# B_Sensor_Board_Digital_v1_2.net
KiCad netlist of a schematic drawn in EAGLE
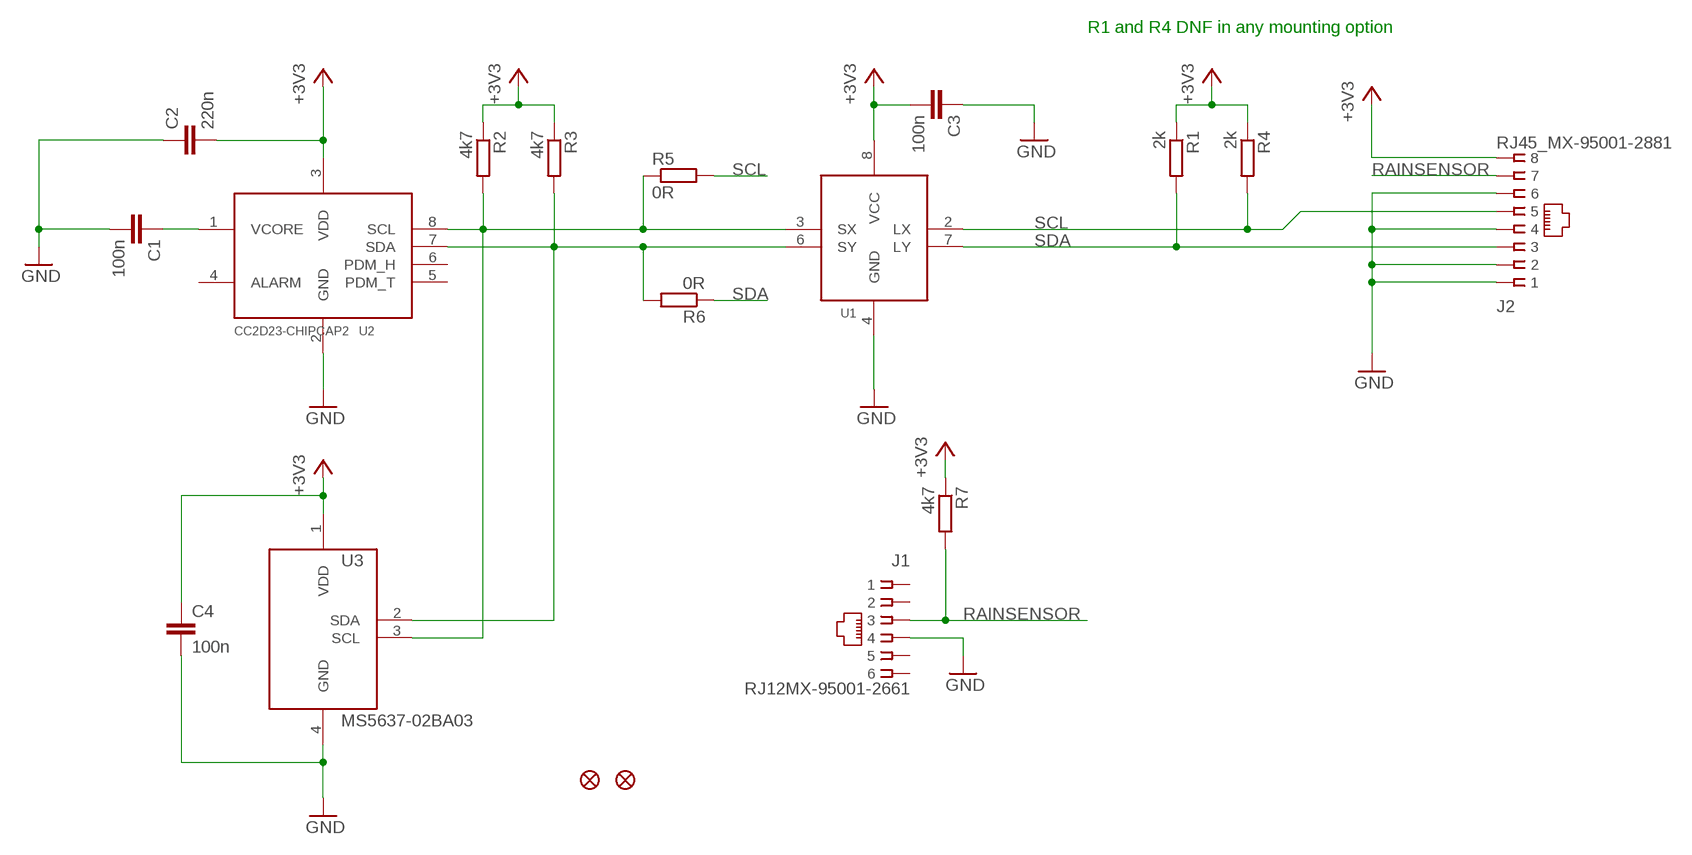
[diagram p0: schematic, sheet 1]

(export (version "E")
  (design (tool "Eeschema 10.0.6"))
  (components
    (comp (ref "C1")
      (value "100n")
      (footprint "eagle-import:C1206")
      (libsource (lib "eagle-import") (part "C-EUC1206"))
    )
    (comp (ref "C2")
      (value "220n")
      (footprint "eagle-import:C1206")
      (libsource (lib "eagle-import") (part "C-EUC1206"))
    )
    (comp (ref "C3")
      (value "100n")
      (footprint "eagle-import:C1206")
      (libsource (lib "eagle-import") (part "C-EUC1206"))
    )
    (comp (ref "C4")
      (value "100n")
      (footprint "eagle-import:C1206")
      (libsource (lib "eagle-import") (part "C-EUC1206"))
    )
    (comp (ref "J1")
      (value "RJ12MX-95001-2661")
      (footprint "eagle-import:MX-95001-2661")
      (libsource (lib "eagle-import") (part "RJ12MX-95001-2661"))
    )
    (comp (ref "J2")
      (value "RJ45_MX-95001-2881")
      (footprint "eagle-import:MX-95001-2881")
      (libsource (lib "eagle-import") (part "RJ45_MX-95001-2881"))
    )
    (comp (ref "JP1")
      (value "FIDUCIALUFIDUCIAL")
      (footprint "eagle-import:MICRO-FIDUCIAL")
      (libsource (lib "eagle-import") (part "FIDUCIALUFIDUCIAL"))
    )
    (comp (ref "JP2")
      (value "FIDUCIALUFIDUCIAL")
      (footprint "eagle-import:MICRO-FIDUCIAL")
      (libsource (lib "eagle-import") (part "FIDUCIALUFIDUCIAL"))
    )
    (comp (ref "R1")
      (value "2k")
      (footprint "eagle-import:R1206")
      (libsource (lib "eagle-import") (part "R-EU_R1206"))
    )
    (comp (ref "R2")
      (value "4k7")
      (footprint "eagle-import:R1206")
      (libsource (lib "eagle-import") (part "R-EU_R1206"))
    )
    (comp (ref "R3")
      (value "4k7")
      (footprint "eagle-import:R1206")
      (libsource (lib "eagle-import") (part "R-EU_R1206"))
    )
    (comp (ref "R4")
      (value "2k")
      (footprint "eagle-import:R1206")
      (libsource (lib "eagle-import") (part "R-EU_R1206"))
    )
    (comp (ref "R5")
      (value "0R")
      (footprint "eagle-import:R1206")
      (libsource (lib "eagle-import") (part "R-EU_R1206"))
    )
    (comp (ref "R6")
      (value "0R")
      (footprint "eagle-import:R1206")
      (libsource (lib "eagle-import") (part "R-EU_R1206"))
    )
    (comp (ref "R7")
      (value "4k7")
      (footprint "eagle-import:R1206")
      (libsource (lib "eagle-import") (part "R-EU_R1206"))
    )
    (comp (ref "U1")
      (value "P82B715_I2C_BUS_EXTENDER")
      (footprint "eagle-import:SO-08")
      (libsource (lib "eagle-import") (part "P82B715_I2C_BUS_EXTENDER"))
    )
    (comp (ref "U2")
      (value "CC2D23-CHIPCAP2")
      (footprint "eagle-import:CC2D23-CHIPCAP2")
      (libsource (lib "eagle-import") (part "CC2D23-CHIPCAP2"))
    )
    (comp (ref "U3")
      (value "MS5637-02BA03")
      (footprint "eagle-import:MS5637-02BA03")
      (libsource (lib "eagle-import") (part "MS5637-02BA03"))
    )
  )
  (nets
    (net (code "1") (name "+3V3") (class "Default")
      (node (ref "C2") (pin "2") (pinfunction "2_2") (pintype "passive"))
      (node (ref "C3") (pin "2") (pinfunction "2_2") (pintype "passive"))
      (node (ref "C4") (pin "1") (pinfunction "1_1") (pintype "passive"))
      (node (ref "J2") (pin "8") (pinfunction "8_8") (pintype "passive"))
      (node (ref "R1") (pin "1") (pinfunction "1_1") (pintype "passive"))
      (node (ref "R2") (pin "1") (pinfunction "1_1") (pintype "passive"))
      (node (ref "R3") (pin "1") (pinfunction "1_1") (pintype "passive"))
      (node (ref "R4") (pin "1") (pinfunction "1_1") (pintype "passive"))
      (node (ref "R7") (pin "1") (pinfunction "1_1") (pintype "passive"))
      (node (ref "U1") (pin "8") (pinfunction "VCC_8") (pintype "bidirectional"))
      (node (ref "U2") (pin "3") (pinfunction "VDD_3") (pintype "bidirectional"))
      (node (ref "U3") (pin "1") (pinfunction "VDD_1") (pintype "power_in"))
    )
    (net (code "2") (name "/RAINSENSOR") (class "Default")
      (node (ref "J1") (pin "3") (pinfunction "3_3") (pintype "passive"))
      (node (ref "J2") (pin "7") (pinfunction "7_7") (pintype "passive"))
      (node (ref "R7") (pin "2") (pinfunction "2_2") (pintype "passive"))
    )
    (net (code "3") (name "/SCL") (class "Default")
      (node (ref "J2") (pin "5") (pinfunction "5_5") (pintype "passive"))
      (node (ref "R4") (pin "2") (pinfunction "2_2") (pintype "passive"))
      (node (ref "R5") (pin "2") (pinfunction "2_2") (pintype "passive"))
      (node (ref "U1") (pin "2") (pinfunction "LX_2") (pintype "bidirectional"))
    )
    (net (code "4") (name "/SDA") (class "Default")
      (node (ref "J2") (pin "3") (pinfunction "3_3") (pintype "passive"))
      (node (ref "R1") (pin "2") (pinfunction "2_2") (pintype "passive"))
      (node (ref "R6") (pin "1") (pinfunction "1_1") (pintype "passive"))
      (node (ref "U1") (pin "7") (pinfunction "LY_7") (pintype "bidirectional"))
    )
    (net (code "5") (name "GND") (class "Default")
      (node (ref "C1") (pin "2") (pinfunction "2_2") (pintype "passive"))
      (node (ref "C2") (pin "1") (pinfunction "1_1") (pintype "passive"))
      (node (ref "C3") (pin "1") (pinfunction "1_1") (pintype "passive"))
      (node (ref "C4") (pin "2") (pinfunction "2_2") (pintype "passive"))
      (node (ref "J1") (pin "4") (pinfunction "4_4") (pintype "passive"))
      (node (ref "J2") (pin "1") (pinfunction "1_1") (pintype "passive"))
      (node (ref "J2") (pin "2") (pinfunction "2_2") (pintype "passive"))
      (node (ref "J2") (pin "4") (pinfunction "4_4") (pintype "passive"))
      (node (ref "J2") (pin "6") (pinfunction "6_6") (pintype "passive"))
      (node (ref "U1") (pin "4") (pinfunction "GND_4") (pintype "bidirectional"))
      (node (ref "U2") (pin "2") (pinfunction "GND_2") (pintype "bidirectional"))
      (node (ref "U3") (pin "4") (pinfunction "GND_4") (pintype "power_in"))
    )
    (net (code "6") (name "Net-(U1-SX)") (class "Default")
      (node (ref "R2") (pin "2") (pinfunction "2_2") (pintype "passive"))
      (node (ref "R5") (pin "1") (pinfunction "1_1") (pintype "passive"))
      (node (ref "U1") (pin "3") (pinfunction "SX_3") (pintype "bidirectional"))
      (node (ref "U2") (pin "8") (pinfunction "SCL_8") (pintype "bidirectional"))
      (node (ref "U3") (pin "3") (pinfunction "SCL_3") (pintype "bidirectional"))
    )
    (net (code "7") (name "Net-(U1-SY)") (class "Default")
      (node (ref "R3") (pin "2") (pinfunction "2_2") (pintype "passive"))
      (node (ref "R6") (pin "2") (pinfunction "2_2") (pintype "passive"))
      (node (ref "U1") (pin "6") (pinfunction "SY_6") (pintype "bidirectional"))
      (node (ref "U2") (pin "7") (pinfunction "SDA_7") (pintype "bidirectional"))
      (node (ref "U3") (pin "2") (pinfunction "SDA_2") (pintype "bidirectional"))
    )
    (net (code "8") (name "Net-(U2-VCORE)") (class "Default")
      (node (ref "C1") (pin "1") (pinfunction "1_1") (pintype "passive"))
      (node (ref "U2") (pin "1") (pinfunction "VCORE_1") (pintype "bidirectional"))
    )
    (net (code "9") (name "unconnected-(J1-Pad1)") (class "Default")
      (node (ref "J1") (pin "1") (pinfunction "1_1") (pintype "passive"))
    )
    (net (code "10") (name "unconnected-(J1-Pad2)") (class "Default")
      (node (ref "J1") (pin "2") (pinfunction "2_2") (pintype "passive"))
    )
    (net (code "11") (name "unconnected-(J1-Pad5)") (class "Default")
      (node (ref "J1") (pin "5") (pinfunction "5_5") (pintype "passive"))
    )
    (net (code "12") (name "unconnected-(J1-Pad6)") (class "Default")
      (node (ref "J1") (pin "6") (pinfunction "6_6") (pintype "passive"))
    )
    (net (code "13") (name "unconnected-(U2-ALARM-Pad4)") (class "Default")
      (node (ref "U2") (pin "4") (pinfunction "ALARM_4") (pintype "bidirectional"))
    )
    (net (code "14") (name "unconnected-(U2-PDM_H-Pad6)") (class "Default")
      (node (ref "U2") (pin "6") (pinfunction "PDM_H_6") (pintype "bidirectional"))
    )
    (net (code "15") (name "unconnected-(U2-PDM_T-Pad5)") (class "Default")
      (node (ref "U2") (pin "5") (pinfunction "PDM_T_5") (pintype "bidirectional"))
    )
  )
)
